# Spectacle_Audio_Output_Board.net
KiCad netlist of a schematic drawn in EAGLE
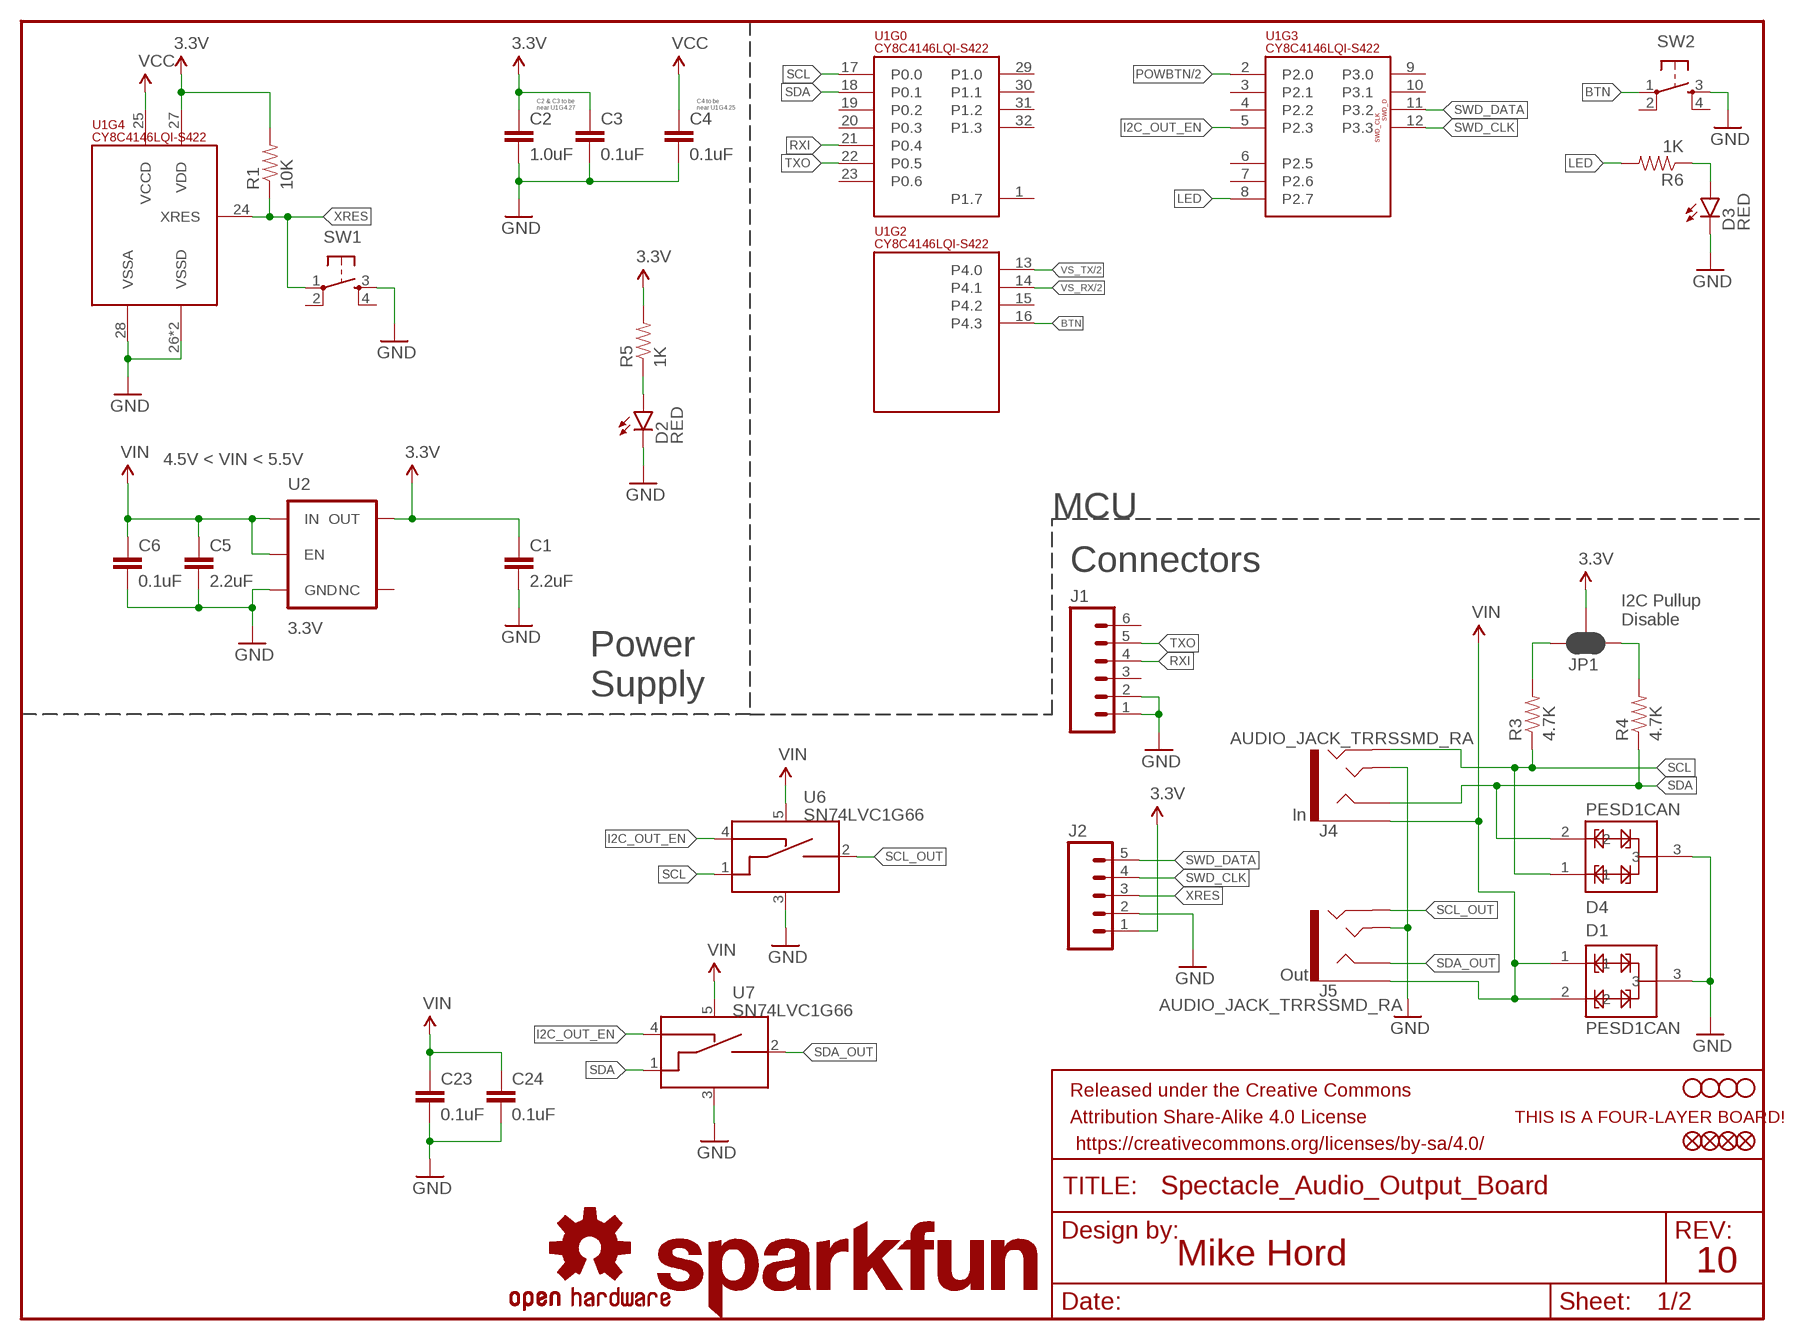
[diagram p0: schematic, sheet 1]
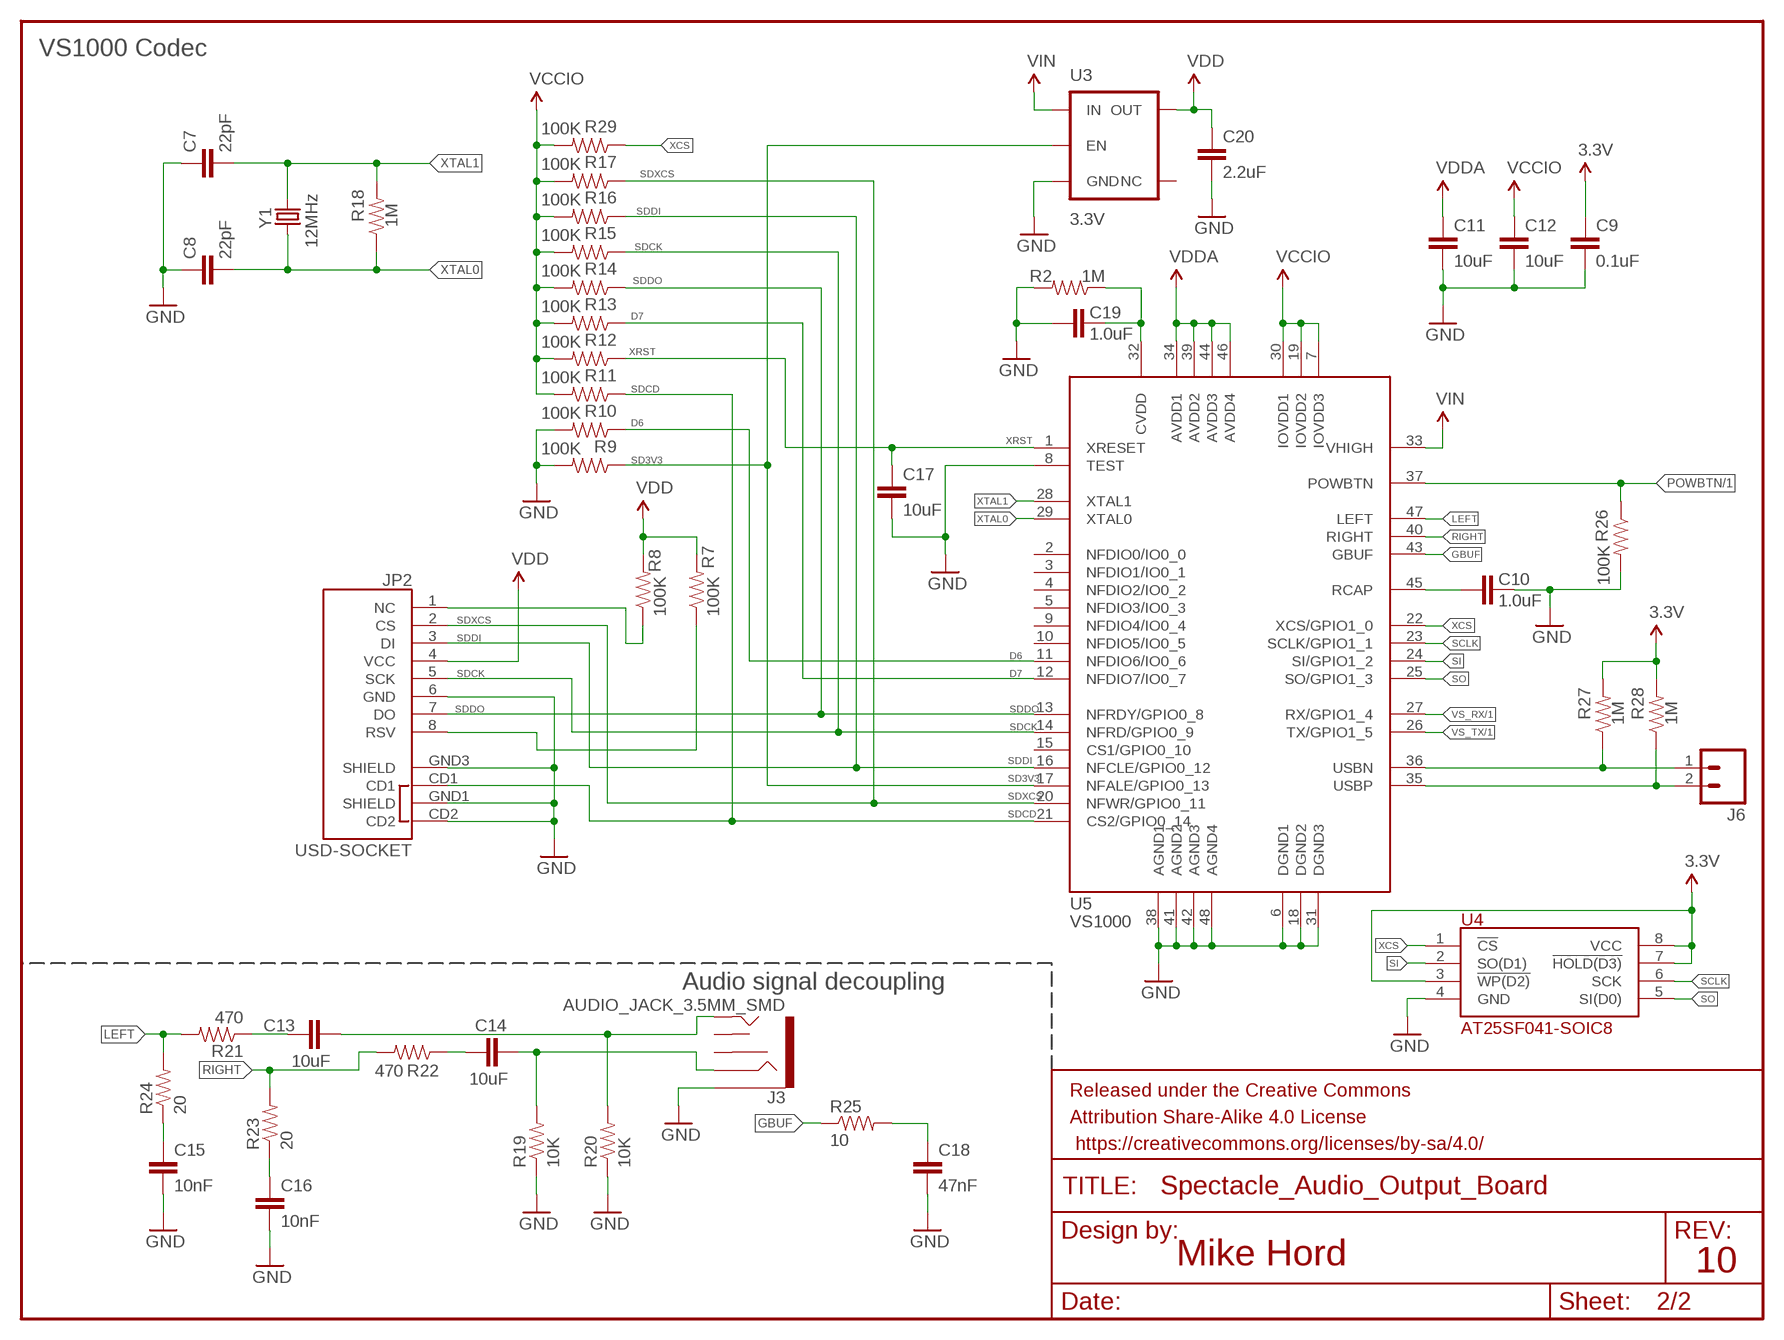
[diagram p1: schematic, sheet 2]

(export (version "E")
  (design (tool "Eeschema 10.0.6"))
  (components
    (comp (ref "C7")
      (value "22pF")
      (footprint "eagle-import:0603-CAP")
      (libsource (lib "eagle-import") (part "22PF-50V-5%(0603)"))
    )
    (comp (ref "C8")
      (value "22pF")
      (footprint "eagle-import:0603-CAP")
      (libsource (lib "eagle-import") (part "22PF-50V-5%(0603)"))
    )
    (comp (ref "C9")
      (value "0.1uF")
      (footprint "eagle-import:0402-CAP")
      (libsource (lib "eagle-import") (part "0.1UF-16V(+-10%)(0402)"))
    )
    (comp (ref "C10")
      (value "1.0uF")
      (footprint "eagle-import:0402-CAP")
      (libsource (lib "eagle-import") (part "1.0UF-16V-10%(0402)"))
    )
    (comp (ref "C11")
      (value "10uF")
      (footprint "eagle-import:0603-CAP")
      (libsource (lib "eagle-import") (part "10UF-6.3V-20%(0603)"))
    )
    (comp (ref "C12")
      (value "10uF")
      (footprint "eagle-import:0603-CAP")
      (libsource (lib "eagle-import") (part "10UF-6.3V-20%(0603)"))
    )
    (comp (ref "C13")
      (value "10uF")
      (footprint "eagle-import:0603-CAP")
      (libsource (lib "eagle-import") (part "10UF-6.3V-20%(0603)"))
    )
    (comp (ref "C14")
      (value "10uF")
      (footprint "eagle-import:0603-CAP")
      (libsource (lib "eagle-import") (part "10UF-6.3V-20%(0603)"))
    )
    (comp (ref "C15")
      (value "10nF")
      (footprint "eagle-import:0603-CAP")
      (libsource (lib "eagle-import") (part "10NF/10000PF-50V-10%(0603)"))
    )
    (comp (ref "C16")
      (value "10nF")
      (footprint "eagle-import:0603-CAP")
      (libsource (lib "eagle-import") (part "10NF/10000PF-50V-10%(0603)"))
    )
    (comp (ref "C17")
      (value "10uF")
      (footprint "eagle-import:0603-CAP")
      (libsource (lib "eagle-import") (part "10UF-6.3V-20%(0603)"))
    )
    (comp (ref "C18")
      (value "47nF")
      (footprint "eagle-import:0603-CAP")
      (libsource (lib "eagle-import") (part "47NF(0.047UF/47000PF)-25V-5%(0603)SMD"))
    )
    (comp (ref "C19")
      (value "1.0uF")
      (footprint "eagle-import:0402-CAP")
      (libsource (lib "eagle-import") (part "1.0UF-16V-10%(0402)"))
    )
    (comp (ref "C20")
      (value "2.2uF")
      (footprint "eagle-import:0603-CAP")
      (libsource (lib "eagle-import") (part "2.2UF-10V-20%(0603)"))
    )
    (comp (ref "FRAME2")
      (value "FRAME-LETTER")
      (footprint "eagle-import:CREATIVE_COMMONS")
      (libsource (lib "eagle-import") (part "FRAME-LETTER"))
    )
    (comp (ref "J3")
      (value "AUDIO_JACK_3.5MM_SMD")
      (footprint "eagle-import:AUDIO-JACK-3.5MM-SMD")
      (libsource (lib "eagle-import") (part "AUDIO_JACK_3.5MM_SMD"))
    )
    (comp (ref "J6")
      (value "M021X02_NO_SILK")
      (footprint "eagle-import:1X02_NO_SILK")
      (libsource (lib "eagle-import") (part "M021X02_NO_SILK"))
    )
    (comp (ref "JP2")
      (value "USD-SOCKET")
      (footprint "eagle-import:MICROSD_1_1")
      (libsource (lib "eagle-import") (part "USD-SOCKET"))
    )
    (comp (ref "R2")
      (value "1M")
      (footprint "eagle-import:0603-RES")
      (libsource (lib "eagle-import") (part "1MOHM-1/10W-1%(0603)"))
    )
    (comp (ref "R7")
      (value "100K")
      (footprint "eagle-import:0402-RES")
      (libsource (lib "eagle-import") (part "100KOHM-1/16W-1%(0402)"))
    )
    (comp (ref "R8")
      (value "100K")
      (footprint "eagle-import:0402-RES")
      (libsource (lib "eagle-import") (part "100KOHM-1/16W-1%(0402)"))
    )
    (comp (ref "R9")
      (value "100K")
      (footprint "eagle-import:0402-RES")
      (libsource (lib "eagle-import") (part "100KOHM-1/16W-1%(0402)"))
    )
    (comp (ref "R10")
      (value "100K")
      (footprint "eagle-import:0402-RES")
      (libsource (lib "eagle-import") (part "100KOHM-1/16W-1%(0402)"))
    )
    (comp (ref "R11")
      (value "100K")
      (footprint "eagle-import:0402-RES")
      (libsource (lib "eagle-import") (part "100KOHM-1/16W-1%(0402)"))
    )
    (comp (ref "R12")
      (value "100K")
      (footprint "eagle-import:0402-RES")
      (libsource (lib "eagle-import") (part "100KOHM-1/16W-1%(0402)"))
    )
    (comp (ref "R13")
      (value "100K")
      (footprint "eagle-import:0402-RES")
      (libsource (lib "eagle-import") (part "100KOHM-1/16W-1%(0402)"))
    )
    (comp (ref "R14")
      (value "100K")
      (footprint "eagle-import:0402-RES")
      (libsource (lib "eagle-import") (part "100KOHM-1/16W-1%(0402)"))
    )
    (comp (ref "R15")
      (value "100K")
      (footprint "eagle-import:0402-RES")
      (libsource (lib "eagle-import") (part "100KOHM-1/16W-1%(0402)"))
    )
    (comp (ref "R16")
      (value "100K")
      (footprint "eagle-import:0402-RES")
      (libsource (lib "eagle-import") (part "100KOHM-1/16W-1%(0402)"))
    )
    (comp (ref "R17")
      (value "100K")
      (footprint "eagle-import:0402-RES")
      (libsource (lib "eagle-import") (part "100KOHM-1/16W-1%(0402)"))
    )
    (comp (ref "R18")
      (value "1M")
      (footprint "eagle-import:0603-RES")
      (libsource (lib "eagle-import") (part "1MOHM-1/10W-1%(0603)"))
    )
    (comp (ref "R19")
      (value "10K")
      (footprint "eagle-import:0603-RES")
      (libsource (lib "eagle-import") (part "10KOHM-1/10W-1%(0603)0603"))
    )
    (comp (ref "R20")
      (value "10K")
      (footprint "eagle-import:0603-RES")
      (libsource (lib "eagle-import") (part "10KOHM-1/10W-1%(0603)0603"))
    )
    (comp (ref "R21")
      (value "470")
      (footprint "eagle-import:0603-RES")
      (libsource (lib "eagle-import") (part "470OHM1/10W1%(0603)"))
    )
    (comp (ref "R22")
      (value "470")
      (footprint "eagle-import:0603-RES")
      (libsource (lib "eagle-import") (part "470OHM1/10W1%(0603)"))
    )
    (comp (ref "R23")
      (value "20")
      (footprint "eagle-import:0603-RES")
      (libsource (lib "eagle-import") (part "20OHM1/10W1%(0603)SMD"))
    )
    (comp (ref "R24")
      (value "20")
      (footprint "eagle-import:0603-RES")
      (libsource (lib "eagle-import") (part "20OHM1/10W1%(0603)SMD"))
    )
    (comp (ref "R25")
      (value "10")
      (footprint "eagle-import:0603-RES")
      (libsource (lib "eagle-import") (part "10OHM-1/10W-5%0603SMD"))
    )
    (comp (ref "R26")
      (value "100K")
      (footprint "eagle-import:0402-RES")
      (libsource (lib "eagle-import") (part "100KOHM-1/16W-1%(0402)"))
    )
    (comp (ref "R27")
      (value "1M")
      (footprint "eagle-import:0603-RES")
      (libsource (lib "eagle-import") (part "1MOHM-1/10W-1%(0603)"))
    )
    (comp (ref "R28")
      (value "1M")
      (footprint "eagle-import:0603-RES")
      (libsource (lib "eagle-import") (part "1MOHM-1/10W-1%(0603)"))
    )
    (comp (ref "R29")
      (value "100K")
      (footprint "eagle-import:0402-RES")
      (libsource (lib "eagle-import") (part "100KOHM-1/16W-1%(0402)"))
    )
    (comp (ref "U3")
      (value "3.3V")
      (footprint "eagle-import:SOT23-5")
      (libsource (lib "eagle-import") (part "V_REG_AP2112K-3.3V"))
    )
    (comp (ref "U4")
      (value "AT25SF041-SOIC8")
      (footprint "eagle-import:SO08")
      (libsource (lib "eagle-import") (part "AT25SF041"))
    )
    (comp (ref "U5")
      (value "VS1000")
      (footprint "eagle-import:LQFP-48")
      (libsource (lib "eagle-import") (part "VS1000"))
    )
    (comp (ref "Y1")
      (value "12MHz")
      (footprint "eagle-import:CRYSTAL-SMD-5X3")
      (libsource (lib "eagle-import") (part "CRYSTALCRYSTAL-SMD-5X3-12MHZ"))
    )
    (comp (ref "C1")
      (value "2.2uF")
      (footprint "eagle-import:0603-CAP")
      (libsource (lib "eagle-import") (part "2.2UF-10V-20%(0603)"))
    )
    (comp (ref "C2")
      (value "1.0uF")
      (footprint "eagle-import:0402-CAP")
      (libsource (lib "eagle-import") (part "1.0UF-16V-10%(0402)"))
    )
    (comp (ref "C3")
      (value "0.1uF")
      (footprint "eagle-import:0402-CAP")
      (libsource (lib "eagle-import") (part "0.1UF-16V(+-10%)(0402)"))
    )
    (comp (ref "C4")
      (value "0.1uF")
      (footprint "eagle-import:0402-CAP")
      (libsource (lib "eagle-import") (part "0.1UF-16V(+-10%)(0402)"))
    )
    (comp (ref "C5")
      (value "2.2uF")
      (footprint "eagle-import:0603-CAP")
      (libsource (lib "eagle-import") (part "2.2UF-10V-20%(0603)"))
    )
    (comp (ref "C6")
      (value "0.1uF")
      (footprint "eagle-import:0402-CAP")
      (libsource (lib "eagle-import") (part "0.1UF-16V(+-10%)(0402)"))
    )
    (comp (ref "C23")
      (value "0.1uF")
      (footprint "eagle-import:0402-CAP")
      (libsource (lib "eagle-import") (part "0.1UF-16V(+-10%)(0402)"))
    )
    (comp (ref "C24")
      (value "0.1uF")
      (footprint "eagle-import:0402-CAP")
      (libsource (lib "eagle-import") (part "0.1UF-16V(+-10%)(0402)"))
    )
    (comp (ref "D1")
      (value "PESD1CAN")
      (footprint "eagle-import:SOT23-3")
      (libsource (lib "eagle-import") (part "PESD1CAN"))
    )
    (comp (ref "D2")
      (value "RED")
      (footprint "eagle-import:LED-0603")
      (libsource (lib "eagle-import") (part "LED-RED0603"))
    )
    (comp (ref "D3")
      (value "RED")
      (footprint "eagle-import:LED-0603")
      (libsource (lib "eagle-import") (part "LED-RED0603"))
    )
    (comp (ref "D4")
      (value "PESD1CAN")
      (footprint "eagle-import:SOT23-3")
      (libsource (lib "eagle-import") (part "PESD1CAN"))
    )
    (comp (ref "FD5")
      (value "FIDUCIALUFIDUCIAL")
      (footprint "eagle-import:MICRO-FIDUCIAL")
      (libsource (lib "eagle-import") (part "FIDUCIALUFIDUCIAL"))
    )
    (comp (ref "FD6")
      (value "FIDUCIALUFIDUCIAL")
      (footprint "eagle-import:MICRO-FIDUCIAL")
      (libsource (lib "eagle-import") (part "FIDUCIALUFIDUCIAL"))
    )
    (comp (ref "FD7")
      (value "FIDUCIALUFIDUCIAL")
      (footprint "eagle-import:MICRO-FIDUCIAL")
      (libsource (lib "eagle-import") (part "FIDUCIALUFIDUCIAL"))
    )
    (comp (ref "FD8")
      (value "FIDUCIALUFIDUCIAL")
      (footprint "eagle-import:MICRO-FIDUCIAL")
      (libsource (lib "eagle-import") (part "FIDUCIALUFIDUCIAL"))
    )
    (comp (ref "FRAME1")
      (value "FRAME-LETTER")
      (footprint "eagle-import:CREATIVE_COMMONS")
      (libsource (lib "eagle-import") (part "FRAME-LETTER"))
    )
    (comp (ref "H1")
      (value "STAND-OFF")
      (footprint "eagle-import:STAND-OFF")
      (libsource (lib "eagle-import") (part "STAND-OFF"))
    )
    (comp (ref "H2")
      (value "STAND-OFF")
      (footprint "eagle-import:STAND-OFF")
      (libsource (lib "eagle-import") (part "STAND-OFF"))
    )
    (comp (ref "H3")
      (value "STAND-OFF")
      (footprint "eagle-import:STAND-OFF")
      (libsource (lib "eagle-import") (part "STAND-OFF"))
    )
    (comp (ref "H4")
      (value "STAND-OFF")
      (footprint "eagle-import:STAND-OFF")
      (libsource (lib "eagle-import") (part "STAND-OFF"))
    )
    (comp (ref "J1")
      (value "M06NO_SILK_NO_POP")
      (footprint "eagle-import:1X06_NO_SILK")
      (libsource (lib "eagle-import") (part "M06NO_SILK_NO_POP"))
    )
    (comp (ref "J2")
      (value "M05NO_SILK")
      (footprint "eagle-import:1X05_NO_SILK")
      (libsource (lib "eagle-import") (part "M05NO_SILK"))
    )
    (comp (ref "J4")
      (value "AUDIO_JACK_TRRSSMD_RA")
      (footprint "eagle-import:AUDIO_JACK_3.5MM_TRRS_SMD_RA")
      (libsource (lib "eagle-import") (part "AUDIO_JACK_TRRSSMD_RA"))
    )
    (comp (ref "J5")
      (value "AUDIO_JACK_TRRSSMD_RA")
      (footprint "eagle-import:AUDIO_JACK_3.5MM_TRRS_SMD_RA")
      (libsource (lib "eagle-import") (part "AUDIO_JACK_TRRSSMD_RA"))
    )
    (comp (ref "JP1")
      (value "JUMPER-PAD-3-NC_BY_PASTE")
      (footprint "eagle-import:PAD-JUMPER-3-NC_BY_PASTE_YES_SILK_FULL_BOX")
      (libsource (lib "eagle-import") (part "JUMPER-PAD-3-NC_BY_PASTE"))
    )
    (comp (ref "LOGO1")
      (value "OSHW-LOGOS")
      (footprint "eagle-import:OSHW-LOGO-S")
      (libsource (lib "eagle-import") (part "OSHW-LOGOS"))
    )
    (comp (ref "LOGO2")
      (value "SFE_LOGO_NAME.1_INCH")
      (footprint "eagle-import:SFE_LOGO_NAME_.1")
      (libsource (lib "eagle-import") (part "SFE_LOGO_NAME.1_INCH"))
    )
    (comp (ref "R1")
      (value "10K")
      (footprint "eagle-import:0603-RES")
      (libsource (lib "eagle-import") (part "10KOHM-1/10W-1%(0603)0603"))
    )
    (comp (ref "R3")
      (value "4.7K")
      (footprint "eagle-import:0603-RES")
      (libsource (lib "eagle-import") (part "4.7KOHM-1/10W-1%(0603)"))
    )
    (comp (ref "R4")
      (value "4.7K")
      (footprint "eagle-import:0603-RES")
      (libsource (lib "eagle-import") (part "4.7KOHM-1/10W-1%(0603)"))
    )
    (comp (ref "R5")
      (value "1K")
      (footprint "eagle-import:0603-RES")
      (libsource (lib "eagle-import") (part "1KOHM-1/10W-1%(0603)"))
    )
    (comp (ref "R6")
      (value "1K")
      (footprint "eagle-import:0603-RES")
      (libsource (lib "eagle-import") (part "1KOHM-1/10W-1%(0603)"))
    )
    (comp (ref "SW1")
      (value "SWITCH_SPST_4_PINRECT")
      (footprint "eagle-import:TACTILE_SWITCH_SMD_4.6X2.8MM")
      (libsource (lib "eagle-import") (part "SWITCH_SPST_4_PINRECT"))
    )
    (comp (ref "SW2")
      (value "SWITCH_SPST_4_PINRECT")
      (footprint "eagle-import:TACTILE_SWITCH_SMD_4.6X2.8MM")
      (libsource (lib "eagle-import") (part "SWITCH_SPST_4_PINRECT"))
    )
    (comp (ref "U$1")
      (value "FOUR_LAYER_WARNING")
      (footprint "eagle-import:FOUR_LAYER_WARNING")
      (libsource (lib "eagle-import") (part "FOUR_LAYER_WARNING"))
    )
    (comp (ref "U1")
      (value "CY8C4146LQI-S422")
      (footprint "eagle-import:QFN-32")
      (libsource (lib "eagle-import") (part "PSOC4_4100S_32QFN"))
    )
    (comp (ref "U2")
      (value "3.3V")
      (footprint "eagle-import:SOT23-5")
      (libsource (lib "eagle-import") (part "V_REG_AP2112K-3.3V"))
    )
    (comp (ref "U6")
      (value "SN74LVC1G66")
      (footprint "eagle-import:SOT23-5")
      (libsource (lib "eagle-import") (part "SN74LVC1G66_SPST_AMUX"))
    )
    (comp (ref "U7")
      (value "SN74LVC1G66")
      (footprint "eagle-import:SOT23-5")
      (libsource (lib "eagle-import") (part "SN74LVC1G66_SPST_AMUX"))
    )
  )
  (nets
    (net (code "1") (name "3.3V") (class "Default")
      (node (ref "C1") (pin "1") (pinfunction "1_1") (pintype "passive"))
      (node (ref "C2") (pin "1") (pinfunction "1_1") (pintype "passive"))
      (node (ref "C3") (pin "1") (pinfunction "1_1") (pintype "passive"))
      (node (ref "C9") (pin "1") (pinfunction "1_1") (pintype "passive"))
      (node (ref "J2") (pin "1") (pinfunction "1_1") (pintype "passive"))
      (node (ref "JP1") (pin "2") (pinfunction "2_2") (pintype "passive"))
      (node (ref "R1") (pin "2") (pinfunction "2_2") (pintype "passive"))
      (node (ref "R27") (pin "2") (pinfunction "2_2") (pintype "passive"))
      (node (ref "R28") (pin "2") (pinfunction "2_2") (pintype "passive"))
      (node (ref "R5") (pin "2") (pinfunction "2_2") (pintype "passive"))
      (node (ref "U1") (pin "27") (pinfunction "VDD_27") (pintype "bidirectional"))
      (node (ref "U2") (pin "5") (pinfunction "OUT_5") (pintype "passive"))
      (node (ref "U4") (pin "3") (pinfunction "~{WP(D2})_3") (pintype "bidirectional"))
      (node (ref "U4") (pin "7") (pinfunction "~{HOLD(D3})_7") (pintype "bidirectional"))
      (node (ref "U4") (pin "8") (pinfunction "VCC_8") (pintype "bidirectional"))
    )
    (net (code "2") (name "BTN") (class "Default")
      (node (ref "SW2") (pin "1") (pinfunction "1_1") (pintype "passive"))
      (node (ref "U1") (pin "16") (pinfunction "P4.3_16") (pintype "bidirectional"))
    )
    (net (code "3") (name "D6") (class "Default")
      (node (ref "R10") (pin "1") (pinfunction "1_1") (pintype "passive"))
      (node (ref "U5") (pin "11") (pinfunction "NFDIO6/IO0_6_11") (pintype "bidirectional"))
    )
    (net (code "4") (name "D7") (class "Default")
      (node (ref "R13") (pin "1") (pinfunction "1_1") (pintype "passive"))
      (node (ref "U5") (pin "12") (pinfunction "NFDIO7/IO0_7_12") (pintype "bidirectional"))
    )
    (net (code "5") (name "GBUF") (class "Default")
      (node (ref "R25") (pin "1") (pinfunction "1_1") (pintype "passive"))
      (node (ref "U5") (pin "43") (pinfunction "GBUF_43") (pintype "bidirectional"))
    )
    (net (code "6") (name "GND") (class "Default")
      (node (ref "C1") (pin "2") (pinfunction "2_2") (pintype "passive"))
      (node (ref "C10") (pin "2") (pinfunction "2_2") (pintype "passive"))
      (node (ref "C11") (pin "2") (pinfunction "2_2") (pintype "passive"))
      (node (ref "C12") (pin "2") (pinfunction "2_2") (pintype "passive"))
      (node (ref "C15") (pin "2") (pinfunction "2_2") (pintype "passive"))
      (node (ref "C16") (pin "2") (pinfunction "2_2") (pintype "passive"))
      (node (ref "C17") (pin "2") (pinfunction "2_2") (pintype "passive"))
      (node (ref "C18") (pin "2") (pinfunction "2_2") (pintype "passive"))
      (node (ref "C19") (pin "1") (pinfunction "1_1") (pintype "passive"))
      (node (ref "C2") (pin "2") (pinfunction "2_2") (pintype "passive"))
      (node (ref "C20") (pin "2") (pinfunction "2_2") (pintype "passive"))
      (node (ref "C23") (pin "2") (pinfunction "2_2") (pintype "passive"))
      (node (ref "C24") (pin "2") (pinfunction "2_2") (pintype "passive"))
      (node (ref "C3") (pin "2") (pinfunction "2_2") (pintype "passive"))
      (node (ref "C4") (pin "2") (pinfunction "2_2") (pintype "passive"))
      (node (ref "C5") (pin "2") (pinfunction "2_2") (pintype "passive"))
      (node (ref "C6") (pin "2") (pinfunction "2_2") (pintype "passive"))
      (node (ref "C7") (pin "1") (pinfunction "1_1") (pintype "passive"))
      (node (ref "C8") (pin "1") (pinfunction "1_1") (pintype "passive"))
      (node (ref "C9") (pin "2") (pinfunction "2_2") (pintype "passive"))
      (node (ref "D1") (pin "3") (pinfunction "3_3") (pintype "bidirectional"))
      (node (ref "D2") (pin "C") (pinfunction "C_C") (pintype "passive"))
      (node (ref "D3") (pin "C") (pinfunction "C_C") (pintype "passive"))
      (node (ref "D4") (pin "3") (pinfunction "3_3") (pintype "bidirectional"))
      (node (ref "J1") (pin "1") (pinfunction "1_1") (pintype "passive"))
      (node (ref "J1") (pin "2") (pinfunction "2_2") (pintype "passive"))
      (node (ref "J2") (pin "2") (pinfunction "2_2") (pintype "passive"))
      (node (ref "J3") (pin "SLEEVE") (pinfunction "SLEEVE_SLEEVE") (pintype "bidirectional"))
      (node (ref "J4") (pin "TIP") (pinfunction "TIP_TIP") (pintype "bidirectional"))
      (node (ref "J5") (pin "TIP") (pinfunction "TIP_TIP") (pintype "bidirectional"))
      (node (ref "JP2") (pin "6") (pinfunction "GND_6") (pintype "bidirectional"))
      (node (ref "JP2") (pin "CD2") (pinfunction "CD2_CD2") (pintype "bidirectional"))
      (node (ref "JP2") (pin "GND1") (pinfunction "SHIELD_GND1") (pintype "bidirectional"))
      (node (ref "JP2") (pin "GND3") (pinfunction "SHIELD_GND3") (pintype "bidirectional"))
      (node (ref "R10") (pin "2") (pinfunction "2_2") (pintype "passive"))
      (node (ref "R19") (pin "1") (pinfunction "1_1") (pintype "passive"))
      (node (ref "R2") (pin "2") (pinfunction "2_2") (pintype "passive"))
      (node (ref "R20") (pin "1") (pinfunction "1_1") (pintype "passive"))
      (node (ref "R26") (pin "2") (pinfunction "2_2") (pintype "passive"))
      (node (ref "R9") (pin "2") (pinfunction "2_2") (pintype "passive"))
      (node (ref "SW1") (pin "3") (pinfunction "3_3") (pintype "passive"))
      (node (ref "SW2") (pin "3") (pinfunction "3_3") (pintype "passive"))
      (node (ref "U1") (pin "26") (pinfunction "VSSD_26") (pintype "bidirectional"))
      (node (ref "U1") (pin "28") (pinfunction "VSSA_28") (pintype "bidirectional"))
      (node (ref "U1") (pin "EP") (pinfunction "VSSD_EP") (pintype "bidirectional"))
      (node (ref "U2") (pin "2") (pinfunction "GND_2") (pintype "input"))
      (node (ref "U3") (pin "2") (pinfunction "GND_2") (pintype "input"))
      (node (ref "U4") (pin "4") (pinfunction "GND_4") (pintype "bidirectional"))
      (node (ref "U5") (pin "18") (pinfunction "DGND2_18") (pintype "bidirectional"))
      (node (ref "U5") (pin "31") (pinfunction "DGND3_31") (pintype "bidirectional"))
      (node (ref "U5") (pin "38") (pinfunction "AGND1_38") (pintype "bidirectional"))
      (node (ref "U5") (pin "41") (pinfunction "AGND2_41") (pintype "bidirectional"))
      (node (ref "U5") (pin "42") (pinfunction "AGND3_42") (pintype "bidirectional"))
      (node (ref "U5") (pin "48") (pinfunction "AGND4_48") (pintype "bidirectional"))
      (node (ref "U5") (pin "6") (pinfunction "DGND1_6") (pintype "bidirectional"))
      (node (ref "U5") (pin "8") (pinfunction "TEST_8") (pintype "bidirectional"))
      (node (ref "U6") (pin "3") (pinfunction "VSS_3") (pintype "bidirectional"))
      (node (ref "U7") (pin "3") (pinfunction "VSS_3") (pintype "bidirectional"))
    )
    (net (code "7") (name "I2C_OUT_EN") (class "Default")
      (node (ref "U1") (pin "5") (pinfunction "P2.3_5") (pintype "bidirectional"))
      (node (ref "U6") (pin "4") (pinfunction "CTRL_IN_4") (pintype "bidirectional"))
      (node (ref "U7") (pin "4") (pinfunction "CTRL_IN_4") (pintype "bidirectional"))
    )
    (net (code "8") (name "LED") (class "Default")
      (node (ref "R6") (pin "2") (pinfunction "2_2") (pintype "passive"))
      (node (ref "U1") (pin "8") (pinfunction "P2.7_8") (pintype "bidirectional"))
    )
    (net (code "9") (name "LEFT") (class "Default")
      (node (ref "R21") (pin "2") (pinfunction "2_2") (pintype "passive"))
      (node (ref "R24") (pin "2") (pinfunction "2_2") (pintype "passive"))
      (node (ref "U5") (pin "47") (pinfunction "LEFT_47") (pintype "bidirectional"))
    )
    (net (code "10") (name "Net-(C13-Pad1)") (class "Default")
      (node (ref "C13") (pin "1") (pinfunction "1_1") (pintype "passive"))
      (node (ref "R21") (pin "1") (pinfunction "1_1") (pintype "passive"))
    )
    (net (code "11") (name "Net-(C13-Pad2)") (class "Default")
      (node (ref "C13") (pin "2") (pinfunction "2_2") (pintype "passive"))
      (node (ref "J3") (pin "TIP") (pinfunction "TIP_TIP") (pintype "bidirectional"))
      (node (ref "R20") (pin "2") (pinfunction "2_2") (pintype "passive"))
    )
    (net (code "12") (name "Net-(C14-Pad1)") (class "Default")
      (node (ref "C14") (pin "1") (pinfunction "1_1") (pintype "passive"))
      (node (ref "R22") (pin "1") (pinfunction "1_1") (pintype "passive"))
    )
    (net (code "13") (name "Net-(C14-Pad2)") (class "Default")
      (node (ref "C14") (pin "2") (pinfunction "2_2") (pintype "passive"))
      (node (ref "J3") (pin "RING") (pinfunction "RING_RING") (pintype "bidirectional"))
      (node (ref "R19") (pin "2") (pinfunction "2_2") (pintype "passive"))
    )
    (net (code "14") (name "Net-(C15-Pad1)") (class "Default")
      (node (ref "C15") (pin "1") (pinfunction "1_1") (pintype "passive"))
      (node (ref "R24") (pin "1") (pinfunction "1_1") (pintype "passive"))
    )
    (net (code "15") (name "Net-(C16-Pad1)") (class "Default")
      (node (ref "C16") (pin "1") (pinfunction "1_1") (pintype "passive"))
      (node (ref "R23") (pin "1") (pinfunction "1_1") (pintype "passive"))
    )
    (net (code "16") (name "Net-(C18-Pad1)") (class "Default")
      (node (ref "C18") (pin "1") (pinfunction "1_1") (pintype "passive"))
      (node (ref "R25") (pin "2") (pinfunction "2_2") (pintype "passive"))
    )
    (net (code "17") (name "Net-(D2-PadA)") (class "Default")
      (node (ref "D2") (pin "A") (pinfunction "A_A") (pintype "passive"))
      (node (ref "R5") (pin "1") (pinfunction "1_1") (pintype "passive"))
    )
    (net (code "18") (name "Net-(D3-PadA)") (class "Default")
      (node (ref "D3") (pin "A") (pinfunction "A_A") (pintype "passive"))
      (node (ref "R6") (pin "1") (pinfunction "1_1") (pintype "passive"))
    )
    (net (code "19") (name "Net-(JP1-Pad1)") (class "Default")
      (node (ref "JP1") (pin "1") (pinfunction "1_1") (pintype "passive"))
      (node (ref "R4") (pin "2") (pinfunction "2_2") (pintype "passive"))
    )
    (net (code "20") (name "Net-(JP1-Pad3)") (class "Default")
      (node (ref "JP1") (pin "3") (pinfunction "3_3") (pintype "passive"))
      (node (ref "R3") (pin "2") (pinfunction "2_2") (pintype "passive"))
    )
    (net (code "21") (name "Net-(JP2-NC)") (class "Default")
      (node (ref "JP2") (pin "1") (pinfunction "NC_1") (pintype "bidirectional"))
      (node (ref "R8") (pin "1") (pinfunction "1_1") (pintype "passive"))
    )
    (net (code "22") (name "Net-(JP2-RSV)") (class "Default")
      (node (ref "JP2") (pin "8") (pinfunction "RSV_8") (pintype "bidirectional"))
      (node (ref "R7") (pin "1") (pinfunction "1_1") (pintype "passive"))
    )
    (net (code "23") (name "Net-(U5-CVDD)") (class "Default")
      (node (ref "C19") (pin "2") (pinfunction "2_2") (pintype "passive"))
      (node (ref "R2") (pin "1") (pinfunction "1_1") (pintype "passive"))
      (node (ref "U5") (pin "32") (pinfunction "CVDD_32") (pintype "bidirectional"))
    )
    (net (code "24") (name "Net-(U5-RCAP)") (class "Default")
      (node (ref "C10") (pin "1") (pinfunction "1_1") (pintype "passive"))
      (node (ref "U5") (pin "45") (pinfunction "RCAP_45") (pintype "bidirectional"))
    )
    (net (code "25") (name "Net-(U5-USBN)") (class "Default")
      (node (ref "J6") (pin "1") (pinfunction "1_1") (pintype "passive"))
      (node (ref "R27") (pin "1") (pinfunction "1_1") (pintype "passive"))
      (node (ref "U5") (pin "36") (pinfunction "USBN_36") (pintype "bidirectional"))
    )
    (net (code "26") (name "Net-(U5-USBP)") (class "Default")
      (node (ref "J6") (pin "2") (pinfunction "2_2") (pintype "passive"))
      (node (ref "R28") (pin "1") (pinfunction "1_1") (pintype "passive"))
      (node (ref "U5") (pin "35") (pinfunction "USBP_35") (pintype "bidirectional"))
    )
    (net (code "27") (name "POWBTN") (class "Default")
      (node (ref "R26") (pin "1") (pinfunction "1_1") (pintype "passive"))
      (node (ref "U1") (pin "2") (pinfunction "P2.0_2") (pintype "bidirectional"))
      (node (ref "U5") (pin "37") (pinfunction "POWBTN_37") (pintype "bidirectional"))
    )
    (net (code "28") (name "RIGHT") (class "Default")
      (node (ref "R22") (pin "2") (pinfunction "2_2") (pintype "passive"))
      (node (ref "R23") (pin "2") (pinfunction "2_2") (pintype "passive"))
      (node (ref "U5") (pin "40") (pinfunction "RIGHT_40") (pintype "bidirectional"))
    )
    (net (code "29") (name "RXI") (class "Default")
      (node (ref "J1") (pin "4") (pinfunction "4_4") (pintype "passive"))
      (node (ref "U1") (pin "21") (pinfunction "P0.4_21") (pintype "bidirectional"))
    )
    (net (code "30") (name "SCL") (class "Default")
      (node (ref "D4") (pin "1") (pinfunction "1_1") (pintype "bidirectional"))
      (node (ref "J4") (pin "RING2") (pinfunction "RING2_RING2") (pintype "bidirectional"))
      (node (ref "R3") (pin "1") (pinfunction "1_1") (pintype "passive"))
      (node (ref "U1") (pin "17") (pinfunction "P0.0_17") (pintype "bidirectional"))
      (node (ref "U6") (pin "1") (pinfunction "A_IN_1") (pintype "bidirectional"))
    )
    (net (code "31") (name "SCLK") (class "Default")
      (node (ref "U4") (pin "6") (pinfunction "SCK_6") (pintype "bidirectional"))
      (node (ref "U5") (pin "23") (pinfunction "SCLK/GPIO1_1_23") (pintype "bidirectional"))
    )
    (net (code "32") (name "SCL_OUT") (class "Default")
      (node (ref "J5") (pin "RING2") (pinfunction "RING2_RING2") (pintype "bidirectional"))
      (node (ref "U6") (pin "2") (pinfunction "A_OUT_2") (pintype "bidirectional"))
    )
    (net (code "33") (name "SD3V3") (class "Default")
      (node (ref "R9") (pin "1") (pinfunction "1_1") (pintype "passive"))
      (node (ref "U3") (pin "3") (pinfunction "EN_3") (pintype "input"))
      (node (ref "U5") (pin "17") (pinfunction "NFALE/GPIO0_13_17") (pintype "bidirectional"))
    )
    (net (code "34") (name "SDA") (class "Default")
      (node (ref "D4") (pin "2") (pinfunction "2_2") (pintype "bidirectional"))
      (node (ref "J4") (pin "RING1") (pinfunction "RING1_RING1") (pintype "bidirectional"))
      (node (ref "R4") (pin "1") (pinfunction "1_1") (pintype "passive"))
      (node (ref "U1") (pin "18") (pinfunction "P0.1_18") (pintype "bidirectional"))
      (node (ref "U7") (pin "1") (pinfunction "A_IN_1") (pintype "bidirectional"))
    )
    (net (code "35") (name "SDA_OUT") (class "Default")
      (node (ref "J5") (pin "RING1") (pinfunction "RING1_RING1") (pintype "bidirectional"))
      (node (ref "U7") (pin "2") (pinfunction "A_OUT_2") (pintype "bidirectional"))
    )
    (net (code "36") (name "SDCD") (class "Default")
      (node (ref "JP2") (pin "CD1") (pinfunction "CD1_CD1") (pintype "bidirectional"))
      (node (ref "R11") (pin "1") (pinfunction "1_1") (pintype "passive"))
      (node (ref "U5") (pin "21") (pinfunction "CS2/GPIO0_14_21") (pintype "bidirectional"))
    )
    (net (code "37") (name "SDCK") (class "Default")
      (node (ref "JP2") (pin "5") (pinfunction "SCK_5") (pintype "bidirectional"))
      (node (ref "R15") (pin "1") (pinfunction "1_1") (pintype "passive"))
      (node (ref "U5") (pin "14") (pinfunction "NFRD/GPIO0_9_14") (pintype "bidirectional"))
    )
    (net (code "38") (name "SDDI") (class "Default")
      (node (ref "JP2") (pin "3") (pinfunction "DI_3") (pintype "bidirectional"))
      (node (ref "R16") (pin "1") (pinfunction "1_1") (pintype "passive"))
      (node (ref "U5") (pin "16") (pinfunction "NFCLE/GPIO0_12_16") (pintype "bidirectional"))
    )
    (net (code "39") (name "SDDO") (class "Default")
      (node (ref "JP2") (pin "7") (pinfunction "DO_7") (pintype "bidirectional"))
      (node (ref "R14") (pin "1") (pinfunction "1_1") (pintype "passive"))
      (node (ref "U5") (pin "13") (pinfunction "NFRDY/GPIO0_8_13") (pintype "bidirectional"))
    )
    (net (code "40") (name "SDXCS") (class "Default")
      (node (ref "JP2") (pin "2") (pinfunction "CS_2") (pintype "bidirectional"))
      (node (ref "R17") (pin "1") (pinfunction "1_1") (pintype "passive"))
      (node (ref "U5") (pin "20") (pinfunction "NFWR/GPIO0_11_20") (pintype "bidirectional"))
    )
    (net (code "41") (name "SI") (class "Default")
      (node (ref "U4") (pin "2") (pinfunction "SO(D1)_2") (pintype "bidirectional"))
      (node (ref "U5") (pin "24") (pinfunction "SI/GPIO1_2_24") (pintype "bidirectional"))
    )
    (net (code "42") (name "SO") (class "Default")
      (node (ref "U4") (pin "5") (pinfunction "SI(D0)_5") (pintype "bidirectional"))
      (node (ref "U5") (pin "25") (pinfunction "SO/GPIO1_3_25") (pintype "bidirectional"))
    )
    (net (code "43") (name "SWD_CLK") (class "Default")
      (node (ref "J2") (pin "4") (pinfunction "4_4") (pintype "passive"))
      (node (ref "U1") (pin "12") (pinfunction "P3.3_12") (pintype "bidirectional"))
    )
    (net (code "44") (name "SWD_DATA") (class "Default")
      (node (ref "J2") (pin "5") (pinfunction "5_5") (pintype "passive"))
      (node (ref "U1") (pin "11") (pinfunction "P3.2_11") (pintype "bidirectional"))
    )
    (net (code "45") (name "TXO") (class "Default")
      (node (ref "J1") (pin "5") (pinfunction "5_5") (pintype "passive"))
      (node (ref "U1") (pin "22") (pinfunction "P0.5_22") (pintype "bidirectional"))
    )
    (net (code "46") (name "VCC") (class "Default")
      (node (ref "C4") (pin "1") (pinfunction "1_1") (pintype "passive"))
      (node (ref "U1") (pin "25") (pinfunction "VCCD_25") (pintype "bidirectional"))
    )
    (net (code "47") (name "VCCIO") (class "Default")
      (node (ref "C12") (pin "1") (pinfunction "1_1") (pintype "passive"))
      (node (ref "R11") (pin "2") (pinfunction "2_2") (pintype "passive"))
      (node (ref "R12") (pin "2") (pinfunction "2_2") (pintype "passive"))
      (node (ref "R13") (pin "2") (pinfunction "2_2") (pintype "passive"))
      (node (ref "R14") (pin "2") (pinfunction "2_2") (pintype "passive"))
      (node (ref "R15") (pin "2") (pinfunction "2_2") (pintype "passive"))
      (node (ref "R16") (pin "2") (pinfunction "2_2") (pintype "passive"))
      (node (ref "R17") (pin "2") (pinfunction "2_2") (pintype "passive"))
      (node (ref "R29") (pin "2") (pinfunction "2_2") (pintype "passive"))
      (node (ref "U5") (pin "19") (pinfunction "IOVDD2_19") (pintype "bidirectional"))
      (node (ref "U5") (pin "30") (pinfunction "IOVDD1_30") (pintype "bidirectional"))
      (node (ref "U5") (pin "7") (pinfunction "IOVDD3_7") (pintype "bidirectional"))
    )
    (net (code "48") (name "VDD") (class "Default")
      (node (ref "C20") (pin "1") (pinfunction "1_1") (pintype "passive"))
      (node (ref "JP2") (pin "4") (pinfunction "VCC_4") (pintype "bidirectional"))
      (node (ref "R7") (pin "2") (pinfunction "2_2") (pintype "passive"))
      (node (ref "R8") (pin "2") (pinfunction "2_2") (pintype "passive"))
      (node (ref "U3") (pin "5") (pinfunction "OUT_5") (pintype "passive"))
    )
    (net (code "49") (name "VDDA") (class "Default")
      (node (ref "C11") (pin "1") (pinfunction "1_1") (pintype "passive"))
      (node (ref "U5") (pin "34") (pinfunction "AVDD1_34") (pintype "bidirectional"))
      (node (ref "U5") (pin "39") (pinfunction "AVDD2_39") (pintype "bidirectional"))
      (node (ref "U5") (pin "44") (pinfunction "AVDD3_44") (pintype "bidirectional"))
      (node (ref "U5") (pin "46") (pinfunction "AVDD4_46") (pintype "bidirectional"))
    )
    (net (code "50") (name "VIN") (class "Default")
      (node (ref "C23") (pin "1") (pinfunction "1_1") (pintype "passive"))
      (node (ref "C24") (pin "1") (pinfunction "1_1") (pintype "passive"))
      (node (ref "C5") (pin "1") (pinfunction "1_1") (pintype "passive"))
      (node (ref "C6") (pin "1") (pinfunction "1_1") (pintype "passive"))
      (node (ref "D1") (pin "1") (pinfunction "1_1") (pintype "bidirectional"))
      (node (ref "D1") (pin "2") (pinfunction "2_2") (pintype "bidirectional"))
      (node (ref "J4") (pin "EARTH") (pinfunction "EARTH_EARTH") (pintype "bidirectional"))
      (node (ref "J5") (pin "EARTH") (pinfunction "EARTH_EARTH") (pintype "bidirectional"))
      (node (ref "U2") (pin "1") (pinfunction "IN_1") (pintype "input"))
      (node (ref "U2") (pin "3") (pinfunction "EN_3") (pintype "input"))
      (node (ref "U3") (pin "1") (pinfunction "IN_1") (pintype "input"))
      (node (ref "U5") (pin "33") (pinfunction "VHIGH_33") (pintype "bidirectional"))
      (node (ref "U6") (pin "5") (pinfunction "VCC_5") (pintype "bidirectional"))
      (node (ref "U7") (pin "5") (pinfunction "VCC_5") (pintype "bidirectional"))
    )
    (net (code "51") (name "VS_RX") (class "Default")
      (node (ref "U1") (pin "14") (pinfunction "P4.1_14") (pintype "bidirectional"))
      (node (ref "U5") (pin "27") (pinfunction "RX/GPIO1_4_27") (pintype "bidirectional"))
    )
    (net (code "52") (name "VS_TX") (class "Default")
      (node (ref "U1") (pin "13") (pinfunction "P4.0_13") (pintype "bidirectional"))
      (node (ref "U5") (pin "26") (pinfunction "TX/GPIO1_5_26") (pintype "bidirectional"))
    )
    (net (code "53") (name "XCS") (class "Default")
      (node (ref "R29") (pin "1") (pinfunction "1_1") (pintype "passive"))
      (node (ref "U4") (pin "1") (pinfunction "~{CS}_1") (pintype "bidirectional"))
      (node (ref "U5") (pin "22") (pinfunction "XCS/GPIO1_0_22") (pintype "bidirectional"))
    )
    (net (code "54") (name "XRES") (class "Default")
      (node (ref "J2") (pin "3") (pinfunction "3_3") (pintype "passive"))
      (node (ref "R1") (pin "1") (pinfunction "1_1") (pintype "passive"))
      (node (ref "SW1") (pin "1") (pinfunction "1_1") (pintype "passive"))
      (node (ref "U1") (pin "24") (pinfunction "XRES_24") (pintype "bidirectional"))
    )
    (net (code "55") (name "XRST") (class "Default")
      (node (ref "C17") (pin "1") (pinfunction "1_1") (pintype "passive"))
      (node (ref "R12") (pin "1") (pinfunction "1_1") (pintype "passive"))
      (node (ref "U5") (pin "1") (pinfunction "XRESET_1") (pintype "bidirectional"))
    )
    (net (code "56") (name "XTAL0") (class "Default")
      (node (ref "C8") (pin "2") (pinfunction "2_2") (pintype "passive"))
      (node (ref "R18") (pin "1") (pinfunction "1_1") (pintype "passive"))
      (node (ref "U5") (pin "29") (pinfunction "XTAL0_29") (pintype "bidirectional"))
      (node (ref "Y1") (pin "1") (pinfunction "1_1") (pintype "passive"))
    )
    (net (code "57") (name "XTAL1") (class "Default")
      (node (ref "C7") (pin "2") (pinfunction "2_2") (pintype "passive"))
      (node (ref "R18") (pin "2") (pinfunction "2_2") (pintype "passive"))
      (node (ref "U5") (pin "28") (pinfunction "XTAL1_28") (pintype "bidirectional"))
      (node (ref "Y1") (pin "3") (pinfunction "2_3") (pintype "passive"))
    )
    (net (code "58") (name "unconnected-(J1-Pad3)") (class "Default")
      (node (ref "J1") (pin "3") (pinfunction "3_3") (pintype "passive"))
    )
    (net (code "59") (name "unconnected-(J1-Pad6)") (class "Default")
      (node (ref "J1") (pin "6") (pinfunction "6_6") (pintype "passive"))
    )
    (net (code "60") (name "unconnected-(J3-PadRSH)") (class "Default")
      (node (ref "J3") (pin "RSH") (pinfunction "RSH_RSH") (pintype "bidirectional"))
    )
    (net (code "61") (name "unconnected-(J3-PadTSH)") (class "Default")
      (node (ref "J3") (pin "TSH") (pinfunction "TSH_TSH") (pintype "bidirectional"))
    )
    (net (code "62") (name "unconnected-(SW1-Pad2)") (class "Default")
      (node (ref "SW1") (pin "2") (pinfunction "2_2") (pintype "passive"))
    )
    (net (code "63") (name "unconnected-(SW1-Pad4)") (class "Default")
      (node (ref "SW1") (pin "4") (pinfunction "4_4") (pintype "passive"))
    )
    (net (code "64") (name "unconnected-(SW2-Pad2)") (class "Default")
      (node (ref "SW2") (pin "2") (pinfunction "2_2") (pintype "passive"))
    )
    (net (code "65") (name "unconnected-(SW2-Pad4)") (class "Default")
      (node (ref "SW2") (pin "4") (pinfunction "4_4") (pintype "passive"))
    )
    (net (code "66") (name "unconnected-(U1A-P0.2-Pad19)") (class "Default")
      (node (ref "U1") (pin "19") (pinfunction "P0.2_19") (pintype "bidirectional"))
    )
    (net (code "67") (name "unconnected-(U1A-P0.3-Pad20)") (class "Default")
      (node (ref "U1") (pin "20") (pinfunction "P0.3_20") (pintype "bidirectional"))
    )
    (net (code "68") (name "unconnected-(U1A-P0.6-Pad23)") (class "Default")
      (node (ref "U1") (pin "23") (pinfunction "P0.6_23") (pintype "bidirectional"))
    )
    (net (code "69") (name "unconnected-(U1A-P1.0-Pad29)") (class "Default")
      (node (ref "U1") (pin "29") (pinfunction "P1.0_29") (pintype "bidirectional"))
    )
    (net (code "70") (name "unconnected-(U1A-P1.1-Pad30)") (class "Default")
      (node (ref "U1") (pin "30") (pinfunction "P1.1_30") (pintype "bidirectional"))
    )
    (net (code "71") (name "unconnected-(U1A-P1.2-Pad31)") (class "Default")
      (node (ref "U1") (pin "31") (pinfunction "P1.2_31") (pintype "bidirectional"))
    )
    (net (code "72") (name "unconnected-(U1A-P1.3-Pad32)") (class "Default")
      (node (ref "U1") (pin "32") (pinfunction "P1.3_32") (pintype "bidirectional"))
    )
    (net (code "73") (name "unconnected-(U1A-P1.7-Pad1)") (class "Default")
      (node (ref "U1") (pin "1") (pinfunction "P1.7_1") (pintype "bidirectional"))
    )
    (net (code "74") (name "unconnected-(U1B-P4.2-Pad15)") (class "Default")
      (node (ref "U1") (pin "15") (pinfunction "P4.2_15") (pintype "bidirectional"))
    )
    (net (code "75") (name "unconnected-(U1C-P2.1-Pad3)") (class "Default")
      (node (ref "U1") (pin "3") (pinfunction "P2.1_3") (pintype "bidirectional"))
    )
    (net (code "76") (name "unconnected-(U1C-P2.2-Pad4)") (class "Default")
      (node (ref "U1") (pin "4") (pinfunction "P2.2_4") (pintype "bidirectional"))
    )
    (net (code "77") (name "unconnected-(U1C-P2.5-Pad6)") (class "Default")
      (node (ref "U1") (pin "6") (pinfunction "P2.5_6") (pintype "bidirectional"))
    )
    (net (code "78") (name "unconnected-(U1C-P2.6-Pad7)") (class "Default")
      (node (ref "U1") (pin "7") (pinfunction "P2.6_7") (pintype "bidirectional"))
    )
    (net (code "79") (name "unconnected-(U1C-P3.0-Pad9)") (class "Default")
      (node (ref "U1") (pin "9") (pinfunction "P3.0_9") (pintype "bidirectional"))
    )
    (net (code "80") (name "unconnected-(U1C-P3.1-Pad10)") (class "Default")
      (node (ref "U1") (pin "10") (pinfunction "P3.1_10") (pintype "bidirectional"))
    )
    (net (code "81") (name "unconnected-(U2-NC-Pad4)") (class "Default")
      (node (ref "U2") (pin "4") (pinfunction "NC_4") (pintype "input"))
    )
    (net (code "82") (name "unconnected-(U3-NC-Pad4)") (class "Default")
      (node (ref "U3") (pin "4") (pinfunction "NC_4") (pintype "input"))
    )
    (net (code "83") (name "unconnected-(U5-CS1{slash}GPIO0_10-Pad15)") (class "Default")
      (node (ref "U5") (pin "15") (pinfunction "CS1/GPIO0_10_15") (pintype "bidirectional"))
    )
    (net (code "84") (name "unconnected-(U5-NFDIO0{slash}IO0_0-Pad2)") (class "Default")
      (node (ref "U5") (pin "2") (pinfunction "NFDIO0/IO0_0_2") (pintype "bidirectional"))
    )
    (net (code "85") (name "unconnected-(U5-NFDIO1{slash}IO0_1-Pad3)") (class "Default")
      (node (ref "U5") (pin "3") (pinfunction "NFDIO1/IO0_1_3") (pintype "bidirectional"))
    )
    (net (code "86") (name "unconnected-(U5-NFDIO2{slash}IO0_2-Pad4)") (class "Default")
      (node (ref "U5") (pin "4") (pinfunction "NFDIO2/IO0_2_4") (pintype "bidirectional"))
    )
    (net (code "87") (name "unconnected-(U5-NFDIO3{slash}IO0_3-Pad5)") (class "Default")
      (node (ref "U5") (pin "5") (pinfunction "NFDIO3/IO0_3_5") (pintype "bidirectional"))
    )
    (net (code "88") (name "unconnected-(U5-NFDIO4{slash}IO0_4-Pad9)") (class "Default")
      (node (ref "U5") (pin "9") (pinfunction "NFDIO4/IO0_4_9") (pintype "bidirectional"))
    )
    (net (code "89") (name "unconnected-(U5-NFDIO5{slash}IO0_5-Pad10)") (class "Default")
      (node (ref "U5") (pin "10") (pinfunction "NFDIO5/IO0_5_10") (pintype "bidirectional"))
    )
  )
)
